# 34.net
KiCad netlist of a schematic drawn in Altium Designer
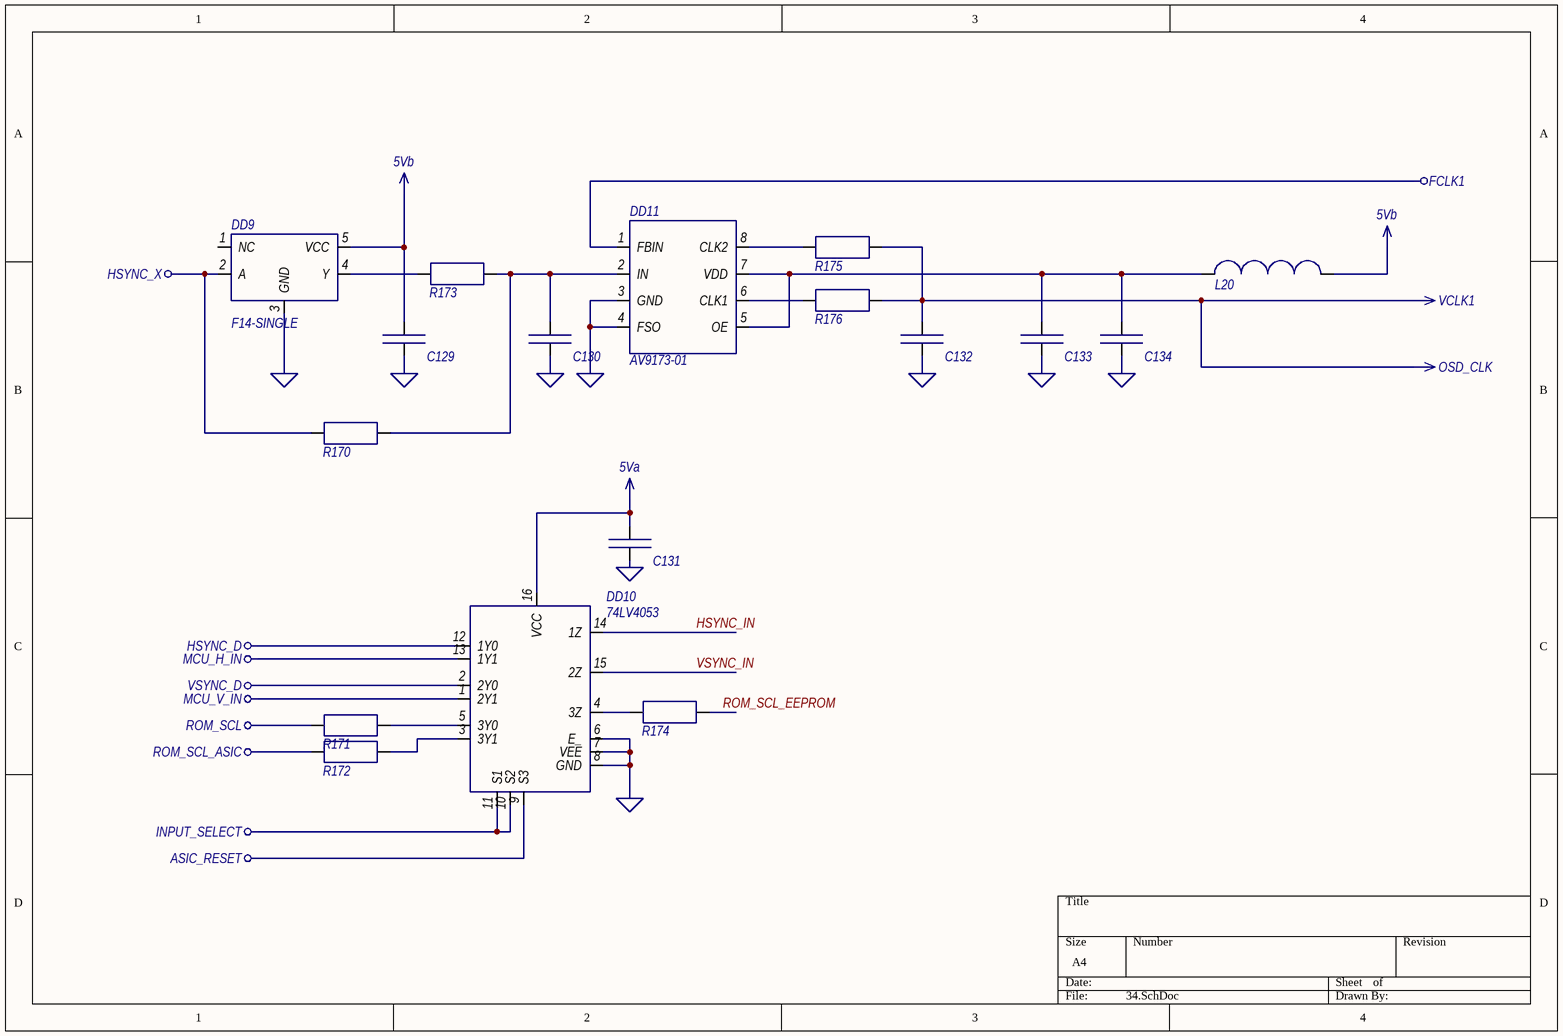
[diagram p0: 34.SchDoc]

(export (version "E")
  (design (tool "Eeschema 10.0.6"))
  (components
    (comp (ref "C129")
      (value "Capacitor")
      (footprint "cap_electro_13")
      (libsource (lib "31_lib") (part "Capacitor"))
    )
    (comp (ref "C130")
      (value "Capacitor")
      (footprint "cap_electro_13")
      (libsource (lib "31_lib") (part "Capacitor"))
    )
    (comp (ref "C131")
      (value "Capacitor")
      (footprint "cap_electro_13")
      (libsource (lib "31_lib") (part "Capacitor"))
    )
    (comp (ref "C132")
      (value "Capacitor")
      (footprint "cap_electro_13")
      (libsource (lib "31_lib") (part "Capacitor"))
    )
    (comp (ref "C133")
      (value "Capacitor")
      (footprint "cap_electro_13")
      (libsource (lib "31_lib") (part "Capacitor"))
    )
    (comp (ref "C134")
      (value "Capacitor")
      (footprint "cap_electro_13")
      (libsource (lib "31_lib") (part "Capacitor"))
    )
    (comp (ref "DD9")
      (value "F14-SINGLE")
      (footprint "74AHC1G14(SOT25)")
      (libsource (lib "31_lib") (part "74AHC1G14-TA"))
    )
    (comp (ref "DD10")
      (value "74LV4053")
      (footprint "31_lib:74LV4053(SOT38-4)")
      (libsource (lib "31_lib") (part "74LV4053"))
    )
    (comp (ref "DD11")
      (value "AV9173-01")
      (footprint "31_lib:AV9173-01(DIP8)")
      (libsource (lib "31_lib") (part "AV9173-01"))
    )
    (comp (ref "L20")
      (value "Inductor")
      (footprint "31_lib:inductor")
      (libsource (lib "31_lib") (part "Inductor"))
    )
    (comp (ref "R170")
      (value "Resistor")
      (footprint "lab_7_footprints:R_1206")
      (libsource (lib "31_lib") (part "Resistor"))
    )
    (comp (ref "R171")
      (value "Resistor")
      (footprint "lab_7_footprints:R_1206")
      (libsource (lib "31_lib") (part "Resistor"))
    )
    (comp (ref "R172")
      (value "Resistor")
      (footprint "lab_7_footprints:R_1206")
      (libsource (lib "31_lib") (part "Resistor"))
    )
    (comp (ref "R173")
      (value "Resistor")
      (footprint "lab_7_footprints:R_1206")
      (libsource (lib "31_lib") (part "Resistor"))
    )
    (comp (ref "R174")
      (value "Resistor")
      (footprint "lab_7_footprints:R_1206")
      (libsource (lib "31_lib") (part "Resistor"))
    )
    (comp (ref "R175")
      (value "Resistor")
      (footprint "lab_7_footprints:R_1206")
      (libsource (lib "31_lib") (part "Resistor"))
    )
    (comp (ref "R176")
      (value "Resistor")
      (footprint "lab_7_footprints:R_1206")
      (libsource (lib "31_lib") (part "Resistor"))
    )
  )
  (nets
    (net (code "1") (name "/HSYNC_IN") (class "Default")
      (node (ref "DD10") (pin "14") (pinfunction "1Z_14") (pintype "passive"))
    )
    (net (code "2") (name "/ROM_SCL_EEPROM") (class "Default")
      (node (ref "R174") (pin "2") (pinfunction "2_2") (pintype "passive"))
    )
    (net (code "3") (name "/VSYNC_IN") (class "Default")
      (node (ref "DD10") (pin "15") (pinfunction "2Z_15") (pintype "passive"))
    )
    (net (code "4") (name "5Va") (class "Default")
      (node (ref "C131") (pin "2") (pinfunction "2_2") (pintype "passive"))
      (node (ref "DD10") (pin "16") (pinfunction "VCC_16") (pintype "passive"))
    )
    (net (code "5") (name "5Vb") (class "Default")
      (node (ref "C129") (pin "1") (pinfunction "1_1") (pintype "passive"))
      (node (ref "DD9") (pin "5") (pinfunction "VCC_5") (pintype "passive"))
      (node (ref "L20") (pin "2") (pinfunction "2_2") (pintype "passive"))
    )
    (net (code "6") (name "ASIC_RESET") (class "Default")
      (node (ref "DD10") (pin "9") (pinfunction "S3_9") (pintype "passive"))
    )
    (net (code "7") (name "FCLK1") (class "Default")
      (node (ref "DD11") (pin "1") (pinfunction "FBIN_1") (pintype "passive"))
    )
    (net (code "8") (name "GND") (class "Default")
      (node (ref "C129") (pin "2") (pinfunction "2_2") (pintype "passive"))
      (node (ref "C130") (pin "2") (pinfunction "2_2") (pintype "passive"))
      (node (ref "C131") (pin "1") (pinfunction "1_1") (pintype "passive"))
      (node (ref "C132") (pin "2") (pinfunction "2_2") (pintype "passive"))
      (node (ref "C133") (pin "2") (pinfunction "2_2") (pintype "passive"))
      (node (ref "C134") (pin "2") (pinfunction "2_2") (pintype "passive"))
      (node (ref "DD10") (pin "6") (pinfunction "E__6") (pintype "passive"))
      (node (ref "DD10") (pin "7") (pinfunction "VEE_7") (pintype "passive"))
      (node (ref "DD10") (pin "8") (pinfunction "GND_8") (pintype "passive"))
      (node (ref "DD11") (pin "3") (pinfunction "GND_3") (pintype "passive"))
      (node (ref "DD11") (pin "4") (pinfunction "FSO_4") (pintype "passive"))
      (node (ref "DD9") (pin "3") (pinfunction "GND_3") (pintype "passive"))
    )
    (net (code "9") (name "HSYNC_D") (class "Default")
      (node (ref "DD10") (pin "12") (pinfunction "1Y0_12") (pintype "passive"))
    )
    (net (code "10") (name "HSYNC_X") (class "Default")
      (node (ref "DD9") (pin "2") (pinfunction "A_2") (pintype "passive"))
      (node (ref "R170") (pin "1") (pinfunction "1_1") (pintype "passive"))
    )
    (net (code "11") (name "INPUT_SELECT") (class "Default")
      (node (ref "DD10") (pin "10") (pinfunction "S2_10") (pintype "passive"))
      (node (ref "DD10") (pin "11") (pinfunction "S1_11") (pintype "passive"))
    )
    (net (code "12") (name "MCU_H_IN") (class "Default")
      (node (ref "DD10") (pin "13") (pinfunction "1Y1_13") (pintype "passive"))
    )
    (net (code "13") (name "MCU_V_IN") (class "Default")
      (node (ref "DD10") (pin "1") (pinfunction "2Y1_1") (pintype "passive"))
    )
    (net (code "14") (name "Net-(DD9-Y)") (class "Default")
      (node (ref "DD9") (pin "4") (pinfunction "Y_4") (pintype "passive"))
      (node (ref "R173") (pin "1") (pinfunction "1_1") (pintype "passive"))
    )
    (net (code "15") (name "Net-(DD10-3Y0)") (class "Default")
      (node (ref "DD10") (pin "5") (pinfunction "3Y0_5") (pintype "passive"))
      (node (ref "R171") (pin "2") (pinfunction "2_2") (pintype "passive"))
    )
    (net (code "16") (name "Net-(DD10-3Y1)") (class "Default")
      (node (ref "DD10") (pin "3") (pinfunction "3Y1_3") (pintype "passive"))
      (node (ref "R172") (pin "2") (pinfunction "2_2") (pintype "passive"))
    )
    (net (code "17") (name "Net-(DD10-3Z)") (class "Default")
      (node (ref "DD10") (pin "4") (pinfunction "3Z_4") (pintype "passive"))
      (node (ref "R174") (pin "1") (pinfunction "1_1") (pintype "passive"))
    )
    (net (code "18") (name "Net-(DD11-CLK1)") (class "Default")
      (node (ref "DD11") (pin "6") (pinfunction "CLK1_6") (pintype "passive"))
      (node (ref "R176") (pin "1") (pinfunction "1_1") (pintype "passive"))
    )
    (net (code "19") (name "Net-(DD11-CLK2)") (class "Default")
      (node (ref "DD11") (pin "8") (pinfunction "CLK2_8") (pintype "passive"))
      (node (ref "R175") (pin "1") (pinfunction "1_1") (pintype "passive"))
    )
    (net (code "20") (name "Net-(DD11-IN)") (class "Default")
      (node (ref "C130") (pin "1") (pinfunction "1_1") (pintype "passive"))
      (node (ref "DD11") (pin "2") (pinfunction "IN_2") (pintype "passive"))
      (node (ref "R170") (pin "2") (pinfunction "2_2") (pintype "passive"))
      (node (ref "R173") (pin "2") (pinfunction "2_2") (pintype "passive"))
    )
    (net (code "21") (name "Net-(DD11-OE)") (class "Default")
      (node (ref "C133") (pin "1") (pinfunction "1_1") (pintype "passive"))
      (node (ref "C134") (pin "1") (pinfunction "1_1") (pintype "passive"))
      (node (ref "DD11") (pin "5") (pinfunction "OE_5") (pintype "passive"))
      (node (ref "DD11") (pin "7") (pinfunction "VDD_7") (pintype "passive"))
      (node (ref "L20") (pin "1") (pinfunction "1_1") (pintype "passive"))
    )
    (net (code "22") (name "OSD_CLK") (class "Default")
      (node (ref "C132") (pin "1") (pinfunction "1_1") (pintype "passive"))
      (node (ref "R175") (pin "2") (pinfunction "2_2") (pintype "passive"))
      (node (ref "R176") (pin "2") (pinfunction "2_2") (pintype "passive"))
    )
    (net (code "23") (name "ROM_SCL") (class "Default")
      (node (ref "R171") (pin "1") (pinfunction "1_1") (pintype "passive"))
    )
    (net (code "24") (name "ROM_SCL_ASIC") (class "Default")
      (node (ref "R172") (pin "1") (pinfunction "1_1") (pintype "passive"))
    )
    (net (code "25") (name "VSYNC_D") (class "Default")
      (node (ref "DD10") (pin "2") (pinfunction "2Y0_2") (pintype "passive"))
    )
    (net (code "26") (name "unconnected-(DD9-NC-Pad1)") (class "Default")
      (node (ref "DD9") (pin "1") (pinfunction "NC_1") (pintype "passive"))
    )
  )
)
